# cpu.net
KiCad netlist of a schematic drawn in Altium Designer
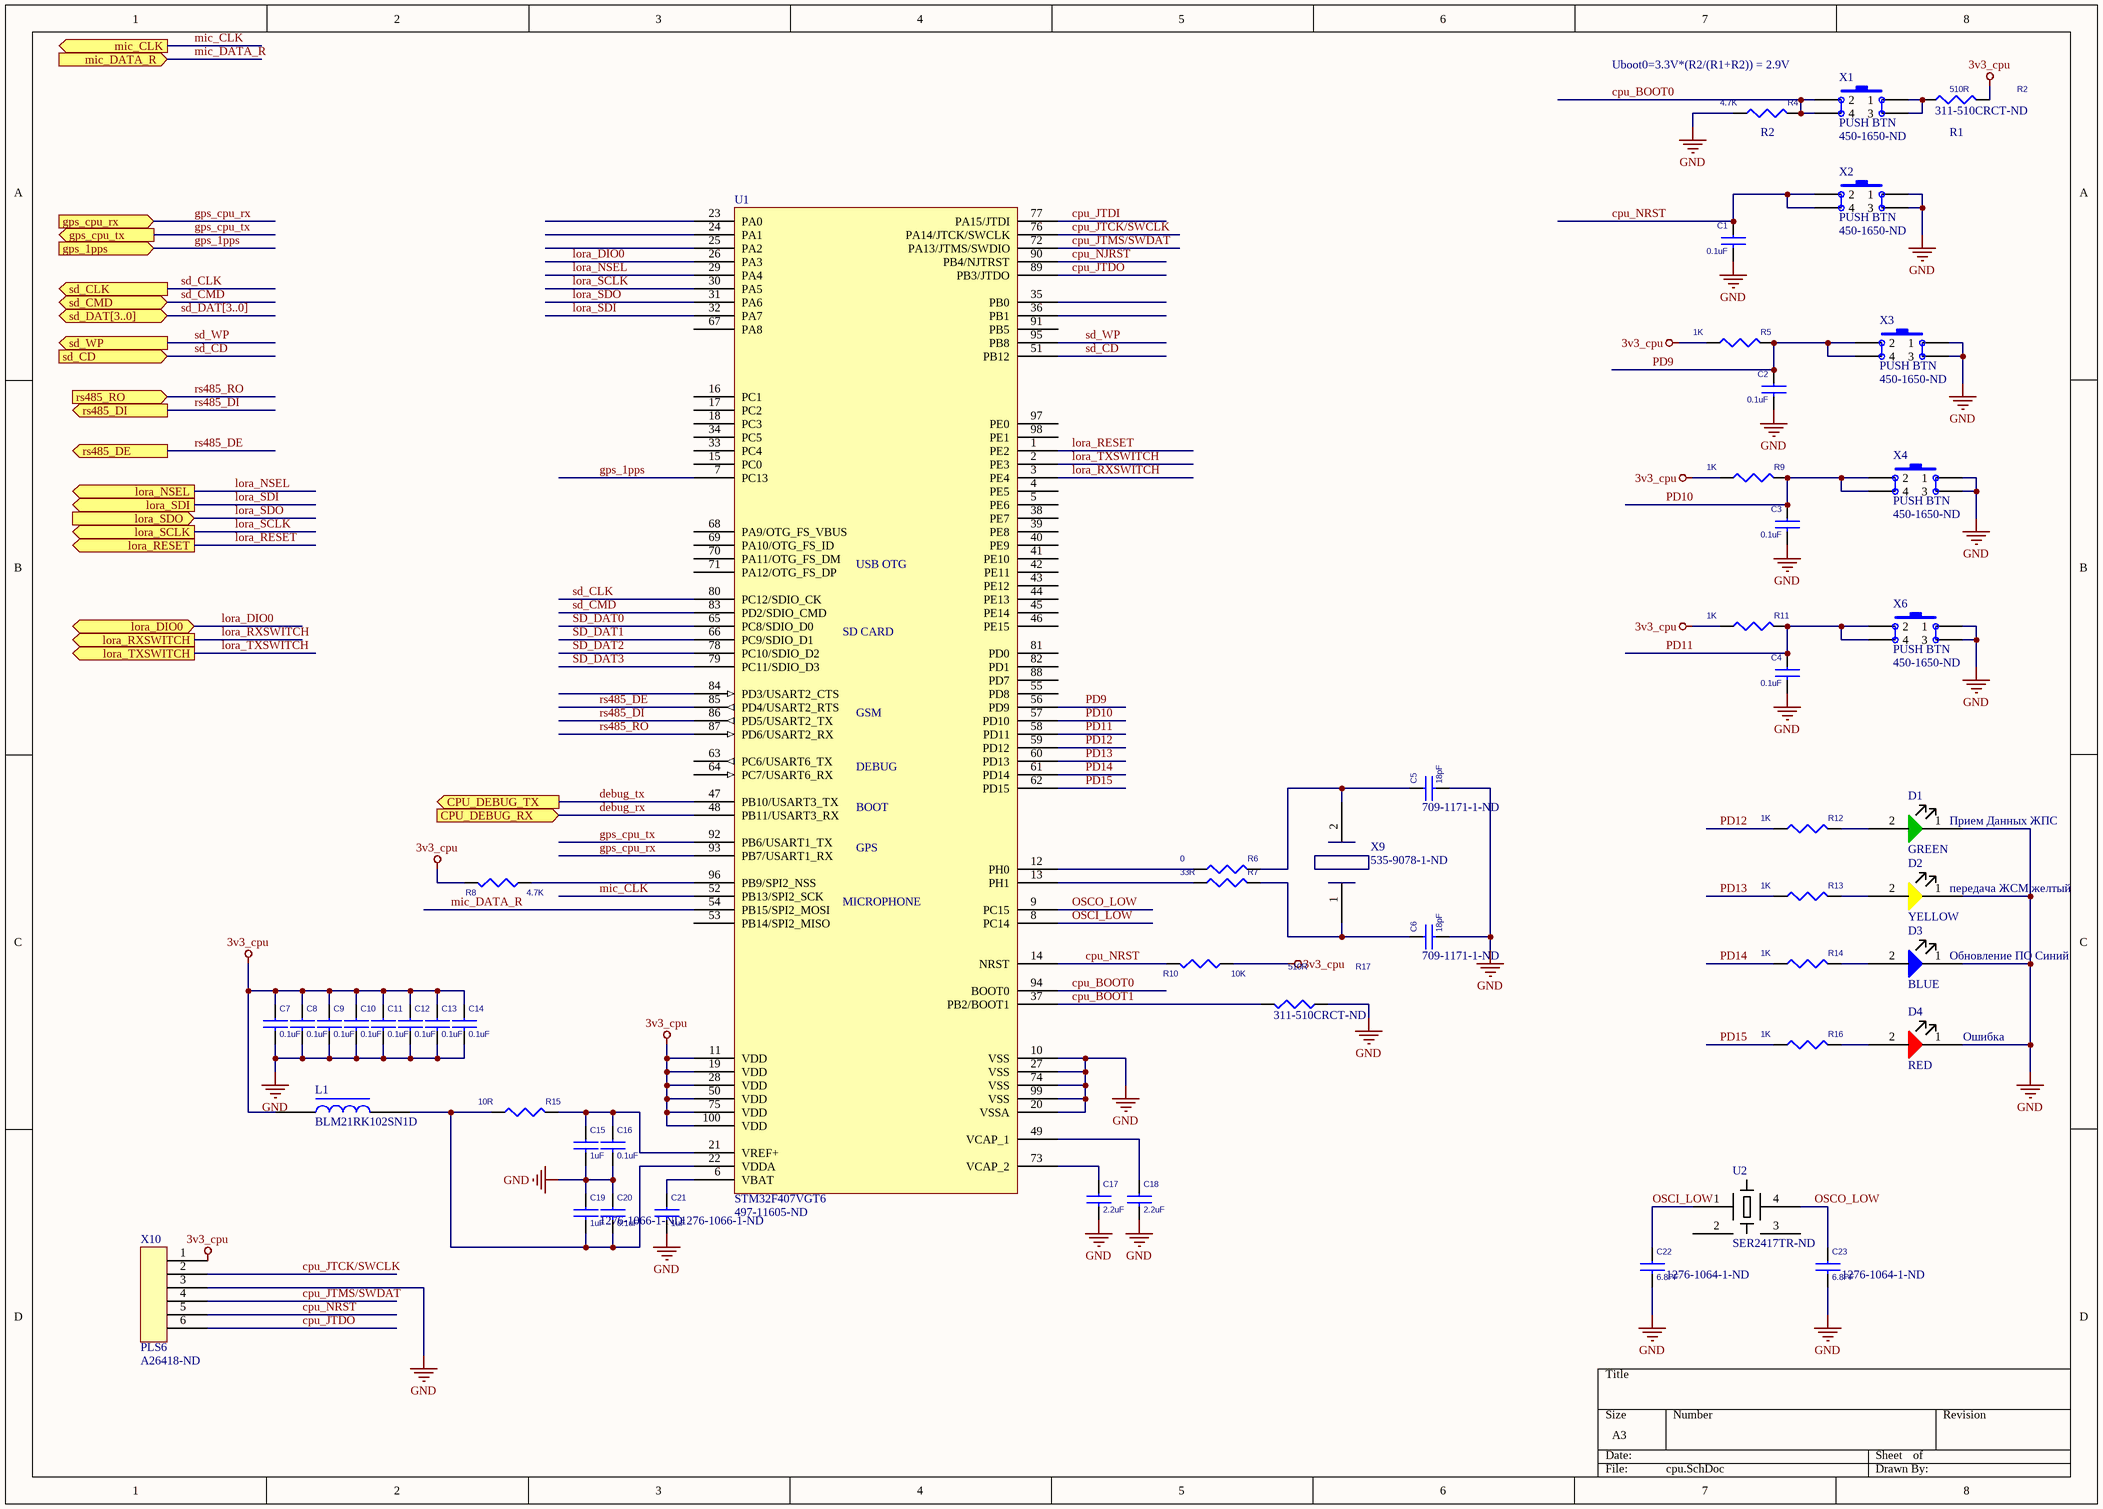
[diagram p0: cpu.SchDoc]

(export (version "E")
  (design (tool "Eeschema 10.0.6"))
  (components
    (comp (ref "C1")
      (value "0.1uF")
      (footprint "CAPC2012X09M")
      (description "CAP CER 0.1UF 25V 10% X7R 0805")
      (libsource (lib "Capacitors") (part "CAP_SMD_0.1UF_10%"))
    )
    (comp (ref "C2")
      (value "0.1uF")
      (footprint "CAPC2012X09M")
      (description "CAP CER 0.1UF 25V 10% X7R 0805")
      (libsource (lib "Capacitors") (part "CAP_SMD_0.1UF_10%"))
    )
    (comp (ref "C3")
      (value "0.1uF")
      (footprint "CAPC2012X09M")
      (description "CAP CER 0.1UF 25V 10% X7R 0805")
      (libsource (lib "Capacitors") (part "CAP_SMD_0.1UF_10%"))
    )
    (comp (ref "C4")
      (value "0.1uF")
      (footprint "CAPC2012X09M")
      (description "CAP CER 0.1UF 25V 10% X7R 0805")
      (libsource (lib "Capacitors") (part "CAP_SMD_0.1UF_10%"))
    )
    (comp (ref "C5")
      (value "18pF")
      (footprint "CAPC2012X09M")
      (description "CAP CER 27PF 200V 5% NP0 0805")
      (fields (field (name "SUPPLIER PART NUMBER 1") "709-1171-1-ND"))
      (libsource (lib "Capacitors") (part "CAP_SMD_18PF_5%"))
    )
    (comp (ref "C6")
      (value "18pF")
      (footprint "CAPC2012X09M")
      (description "CAP CER 27PF 200V 5% NP0 0805")
      (fields (field (name "SUPPLIER PART NUMBER 1") "709-1171-1-ND"))
      (libsource (lib "Capacitors") (part "CAP_SMD_18PF_5%"))
    )
    (comp (ref "C7")
      (value "0.1uF")
      (footprint "CAPC2012X09M")
      (description "CAP CER 0.1UF 25V 10% X7R 0805")
      (libsource (lib "Capacitors") (part "CAP_SMD_0.1UF_10%"))
    )
    (comp (ref "C8")
      (value "0.1uF")
      (footprint "CAPC2012X09M")
      (description "CAP CER 0.1UF 25V 10% X7R 0805")
      (libsource (lib "Capacitors") (part "CAP_SMD_0.1UF_10%"))
    )
    (comp (ref "C9")
      (value "0.1uF")
      (footprint "CAPC2012X09M")
      (description "CAP CER 0.1UF 25V 10% X7R 0805")
      (libsource (lib "Capacitors") (part "CAP_SMD_0.1UF_10%"))
    )
    (comp (ref "C10")
      (value "0.1uF")
      (footprint "CAPC2012X09M")
      (description "CAP CER 0.1UF 25V 10% X7R 0805")
      (libsource (lib "Capacitors") (part "CAP_SMD_0.1UF_10%"))
    )
    (comp (ref "C11")
      (value "0.1uF")
      (footprint "CAPC2012X09M")
      (description "CAP CER 0.1UF 25V 10% X7R 0805")
      (libsource (lib "Capacitors") (part "CAP_SMD_0.1UF_10%"))
    )
    (comp (ref "C12")
      (value "0.1uF")
      (footprint "CAPC2012X09M")
      (description "CAP CER 0.1UF 25V 10% X7R 0805")
      (libsource (lib "Capacitors") (part "CAP_SMD_0.1UF_10%"))
    )
    (comp (ref "C13")
      (value "0.1uF")
      (footprint "CAPC2012X09M")
      (description "CAP CER 0.1UF 25V 10% X7R 0805")
      (libsource (lib "Capacitors") (part "CAP_SMD_0.1UF_10%"))
    )
    (comp (ref "C14")
      (value "0.1uF")
      (footprint "CAPC2012X09M")
      (description "CAP CER 0.1UF 25V 10% X7R 0805")
      (libsource (lib "Capacitors") (part "CAP_SMD_0.1UF_10%"))
    )
    (comp (ref "C15")
      (value "1uF")
      (footprint "CAPC2012X09M")
      (description "MLCC; 1uF; 25V; X7R; ±10%; SMD; 0805;")
      (libsource (lib "Capacitors") (part "CAP_SMD_1uF_10%"))
    )
    (comp (ref "C16")
      (value "0.1uF")
      (footprint "CAPC2012X09M")
      (description "CAP CER 0.1UF 25V 10% X7R 0805")
      (libsource (lib "Capacitors") (part "CAP_SMD_0.1UF_10%"))
    )
    (comp (ref "C17")
      (value "2.2uF")
      (footprint "CAPC2012X09M")
      (description "CAP CER 2.2UF 16V 10% X5R 0805")
      (libsource (lib "Capacitors") (part "CAP_SMD_2.2uF_10%"))
    )
    (comp (ref "C18")
      (value "2.2uF")
      (footprint "CAPC2012X09M")
      (description "CAP CER 2.2UF 16V 10% X5R 0805")
      (libsource (lib "Capacitors") (part "CAP_SMD_2.2uF_10%"))
    )
    (comp (ref "C19")
      (value "1uF")
      (footprint "CAPC2012X09M")
      (description "MLCC; 1uF; 25V; X7R; ±10%; SMD; 0805;")
      (fields (field (name "SUPPLIER PART NUMBER 1") "1276-1066-1-ND"))
      (libsource (lib "Capacitors") (part "CAP_SMD_1uF_10%"))
    )
    (comp (ref "C20")
      (value "0.1uF")
      (footprint "CAPC2012X09M")
      (description "CAP CER 0.1UF 25V 10% X7R 0805")
      (libsource (lib "Capacitors") (part "CAP_SMD_0.1UF_10%"))
    )
    (comp (ref "C21")
      (value "1uF")
      (footprint "CAPC2012X09M")
      (description "MLCC; 1uF; 25V; X7R; ±10%; SMD; 0805;")
      (fields (field (name "SUPPLIER PART NUMBER 1") "1276-1066-1-ND"))
      (libsource (lib "Capacitors") (part "CAP_SMD_1uF_10%"))
    )
    (comp (ref "C22")
      (value "6.8PF")
      (footprint "CAPC2012X09M")
      (description "CAP MLCC 6.8PF 50V 5% NP0 0805")
      (fields (field (name "SUPPLIER PART NUMBER 1") "1276-1064-1-ND"))
      (libsource (lib "Capacitors") (part "CAP_SMD_6.8PF_5%"))
    )
    (comp (ref "C23")
      (value "6.8PF")
      (footprint "CAPC2012X09M")
      (description "CAP MLCC 6.8PF 50V 5% NP0 0805")
      (fields (field (name "SUPPLIER PART NUMBER 1") "1276-1064-1-ND"))
      (libsource (lib "Capacitors") (part "CAP_SMD_6.8PF_5%"))
    )
    (comp (ref "D1")
      (value "GREEN")
      (footprint "DIOC2012X11N")
      (libsource (lib "Passive") (part "LED_GREEN"))
    )
    (comp (ref "D2")
      (value "YELLOW")
      (footprint "DIOC2012X11N")
      (libsource (lib "Passive") (part "LED_YELLOW"))
    )
    (comp (ref "D3") (value "BLUE") (footprint "DIOC2012X11N") (libsource (lib "Passive") (part "LED_BLUE")))
    (comp (ref "D4") (value "RED") (footprint "DIOC2012X11N") (libsource (lib "Passive") (part "LED_RED")))
    (comp (ref "L1")
      (value "BLM21RK102SN1D")
      (footprint "DIOC2012X11N")
      (libsource (lib "Passive") (part "BLM21RK102SN1D"))
    )
    (comp (ref "R2")
      (value "510R")
      (footprint "RESC2013X06M")
      (description "RES - 510 OHM, 5%, 1/8W, 0805 SMD")
      (fields (field (name "SUPPLIER PART NUMBER 1") "311-510CRCT-ND"))
      (libsource (lib "Resistors") (part "RES_SMD_510_5%"))
    )
    (comp (ref "R4")
      (value "4.7K")
      (footprint "RESC2013X06M")
      (description "RES 4.7K OHM 1/8W 1% 0805 SMD")
      (libsource (lib "Resistors") (part "RES_SMD_4.7K_1%"))
    )
    (comp (ref "R5")
      (value "1K")
      (footprint "RESC2013X06M")
      (description "RES - 1K OHM, 5%, 1/8W, 0805 SMD")
      (libsource (lib "Resistors") (part "RES_SMD_1K_5%"))
    )
    (comp (ref "R6")
      (value "0")
      (footprint "RESC2013X06M")
      (description "RES 0.0 OHM 1/8W JUMP 0805 SMD")
      (libsource (lib "Resistors") (part "RES_SMD_0"))
    )
    (comp (ref "R7")
      (value "33R")
      (footprint "RESC2013X06M")
      (description "RES - 33 OHM, 5%, 1/8W, 0805 SMD")
      (libsource (lib "Resistors") (part "RES_SMD_33R_5%"))
    )
    (comp (ref "R8")
      (value "4.7K")
      (footprint "RESC2013X06M")
      (description "RES 4.7K OHM 1/8W 1% 0805 SMD")
      (libsource (lib "Resistors") (part "RES_SMD_4.7K_1%"))
    )
    (comp (ref "R9")
      (value "1K")
      (footprint "RESC2013X06M")
      (description "RES - 1K OHM, 5%, 1/8W, 0805 SMD")
      (libsource (lib "Resistors") (part "RES_SMD_1K_5%"))
    )
    (comp (ref "R10")
      (value "10K")
      (footprint "RESC2013X06M")
      (description "RES 10K OHM 1/8W 5% 0805 SMD")
      (libsource (lib "Resistors") (part "RES_SMD_10K_5%"))
    )
    (comp (ref "R11")
      (value "1K")
      (footprint "RESC2013X06M")
      (description "RES - 1K OHM, 5%, 1/8W, 0805 SMD")
      (libsource (lib "Resistors") (part "RES_SMD_1K_5%"))
    )
    (comp (ref "R12")
      (value "1K")
      (footprint "RESC2013X06M")
      (description "RES - 1K OHM, 5%, 1/8W, 0805 SMD")
      (libsource (lib "Resistors") (part "RES_SMD_1K_5%"))
    )
    (comp (ref "R13")
      (value "1K")
      (footprint "RESC2013X06M")
      (description "RES - 1K OHM, 5%, 1/8W, 0805 SMD")
      (libsource (lib "Resistors") (part "RES_SMD_1K_5%"))
    )
    (comp (ref "R14")
      (value "1K")
      (footprint "RESC2013X06M")
      (description "RES - 1K OHM, 5%, 1/8W, 0805 SMD")
      (libsource (lib "Resistors") (part "RES_SMD_1K_5%"))
    )
    (comp (ref "R15")
      (value "10R")
      (footprint "RESC2013X06M")
      (description "RES 10 OHM 1/8W 1% 0805 SMD")
      (libsource (lib "Resistors") (part "RES_SMD_10R_5%"))
    )
    (comp (ref "R16")
      (value "1K")
      (footprint "RESC2013X06M")
      (description "RES - 1K OHM, 5%, 1/8W, 0805 SMD")
      (libsource (lib "Resistors") (part "RES_SMD_1K_5%"))
    )
    (comp (ref "R17")
      (value "510R")
      (footprint "RESC2013X06M")
      (description "RES - 510 OHM, 5%, 1/8W, 0805 SMD")
      (fields (field (name "SUPPLIER PART NUMBER 1") "311-510CRCT-ND"))
      (libsource (lib "Resistors") (part "RES_SMD_510_5%"))
    )
    (comp (ref "U1")
      (value "STM32F407VGT6")
      (footprint "TSQFP50P1600X1600X160-100M")
      (fields (field (name "SUPPLIER PART NUMBER 1") "497-11605-ND"))
      (libsource (lib "TruthEar") (part "STM32F407VGT6"))
    )
    (comp (ref "U2")
      (value "32.768KHZ")
      (footprint "SOJ550P380X254-4M")
      (fields (field (name "SUPPLIER PART NUMBER 1") "SER2417TR-ND"))
      (libsource (lib "TruthEar") (part "MC-306"))
    )
    (comp (ref "X1")
      (value "PUSH BTN")
      (footprint "PUSHBTN")
      (fields (field (name "SUPPLIER PART NUMBER 1") "450-1650-ND"))
      (libsource (lib "TruthEar") (part "SW1"))
    )
    (comp (ref "X2")
      (value "PUSH BTN")
      (footprint "PUSHBTN")
      (fields (field (name "SUPPLIER PART NUMBER 1") "450-1650-ND"))
      (libsource (lib "TruthEar") (part "SW1"))
    )
    (comp (ref "X3")
      (value "PUSH BTN")
      (footprint "PUSHBTN")
      (fields (field (name "SUPPLIER PART NUMBER 1") "450-1650-ND"))
      (libsource (lib "TruthEar") (part "SW1"))
    )
    (comp (ref "X4")
      (value "PUSH BTN")
      (footprint "PUSHBTN")
      (fields (field (name "SUPPLIER PART NUMBER 1") "450-1650-ND"))
      (libsource (lib "TruthEar") (part "SW1"))
    )
    (comp (ref "X6")
      (value "PUSH BTN")
      (footprint "PUSHBTN")
      (fields (field (name "SUPPLIER PART NUMBER 1") "450-1650-ND"))
      (libsource (lib "TruthEar") (part "SW1"))
    )
    (comp (ref "X9")
      (value "25.000Mhz")
      (footprint "SODFL1270X420-2L")
      (fields (field (name "SUPPLIER PART NUMBER 1") "535-9078-1-ND"))
      (libsource (lib "TruthEar") (part "OSC25M"))
    )
    (comp (ref "X10")
      (value "PLS6")
      (footprint "PLS6")
      (fields (field (name "SUPPLIER PART NUMBER 1") "A26418-ND"))
      (libsource (lib "Connectors") (part "PLS6"))
    )
  )
  (nets
    (net (code "5") (name "/OSCI_LOW") (class "Default")
      (node (ref "C22") (pin "1") (pinfunction "1_1") (pintype "passive"))
      (node (ref "U1") (pin "8") (pinfunction "PC14_8") (pintype "passive"))
      (node (ref "U2") (pin "1") (pinfunction "OSC1_1") (pintype "power_in"))
    )
    (net (code "6") (name "/OSCO_LOW") (class "Default")
      (node (ref "C23") (pin "1") (pinfunction "1_1") (pintype "passive"))
      (node (ref "U1") (pin "9") (pinfunction "PC15_9") (pintype "passive"))
      (node (ref "U2") (pin "4") (pinfunction "OSC2_4") (pintype "power_in"))
    )
    (net (code "7") (name "/PD9") (class "Default")
      (node (ref "C2") (pin "1") (pinfunction "1_1") (pintype "passive"))
      (node (ref "R5") (pin "2") (pinfunction "2_2") (pintype "passive"))
      (node (ref "U1") (pin "56") (pinfunction "PD9_56") (pintype "passive"))
      (node (ref "X3") (pin "2") (pinfunction "2_2") (pintype "passive"))
      (node (ref "X3") (pin "4") (pinfunction "4_4") (pintype "passive"))
    )
    (net (code "8") (name "/PD10") (class "Default")
      (node (ref "C3") (pin "1") (pinfunction "1_1") (pintype "passive"))
      (node (ref "R9") (pin "2") (pinfunction "2_2") (pintype "passive"))
      (node (ref "U1") (pin "57") (pinfunction "PD10_57") (pintype "passive"))
      (node (ref "X4") (pin "2") (pinfunction "2_2") (pintype "passive"))
      (node (ref "X4") (pin "4") (pinfunction "4_4") (pintype "passive"))
    )
    (net (code "9") (name "/PD11") (class "Default")
      (node (ref "C4") (pin "1") (pinfunction "1_1") (pintype "passive"))
      (node (ref "R11") (pin "2") (pinfunction "2_2") (pintype "passive"))
      (node (ref "U1") (pin "58") (pinfunction "PD11_58") (pintype "passive"))
      (node (ref "X6") (pin "2") (pinfunction "2_2") (pintype "passive"))
      (node (ref "X6") (pin "4") (pinfunction "4_4") (pintype "passive"))
    )
    (net (code "10") (name "/PD12") (class "Default")
      (node (ref "R12") (pin "1") (pinfunction "1_1") (pintype "passive"))
      (node (ref "U1") (pin "59") (pinfunction "PD12_59") (pintype "passive"))
    )
    (net (code "11") (name "/PD13") (class "Default")
      (node (ref "R13") (pin "1") (pinfunction "1_1") (pintype "passive"))
      (node (ref "U1") (pin "60") (pinfunction "PD13_60") (pintype "passive"))
    )
    (net (code "12") (name "/PD14") (class "Default")
      (node (ref "R14") (pin "1") (pinfunction "1_1") (pintype "passive"))
      (node (ref "U1") (pin "61") (pinfunction "PD14_61") (pintype "passive"))
    )
    (net (code "13") (name "/PD15") (class "Default")
      (node (ref "R16") (pin "1") (pinfunction "1_1") (pintype "passive"))
      (node (ref "U1") (pin "62") (pinfunction "PD15_62") (pintype "passive"))
    )
    (net (code "14") (name "/SD_DAT0") (class "Default")
      (node (ref "U1") (pin "65") (pinfunction "PC8/SDIO_D0_65") (pintype "passive"))
    )
    (net (code "15") (name "/SD_DAT1") (class "Default")
      (node (ref "U1") (pin "66") (pinfunction "PC9/SDIO_D1_66") (pintype "passive"))
    )
    (net (code "16") (name "/SD_DAT2") (class "Default")
      (node (ref "U1") (pin "78") (pinfunction "PC10/SDIO_D2_78") (pintype "passive"))
    )
    (net (code "17") (name "/SD_DAT3") (class "Default")
      (node (ref "U1") (pin "79") (pinfunction "PC11/SDIO_D3_79") (pintype "passive"))
    )
    (net (code "18") (name "/cpu_BOOT0") (class "Default")
      (node (ref "R4") (pin "2") (pinfunction "2_2") (pintype "passive"))
      (node (ref "U1") (pin "94") (pinfunction "BOOT0_94") (pintype "passive"))
      (node (ref "X1") (pin "2") (pinfunction "2_2") (pintype "passive"))
      (node (ref "X1") (pin "4") (pinfunction "4_4") (pintype "passive"))
    )
    (net (code "19") (name "/cpu_BOOT1") (class "Default")
      (node (ref "R17") (pin "2") (pinfunction "2_2") (pintype "passive"))
      (node (ref "U1") (pin "37") (pinfunction "PB2/BOOT1_37") (pintype "passive"))
    )
    (net (code "20") (name "/cpu_JTCK{slash}SWCLK") (class "Default")
      (node (ref "U1") (pin "76") (pinfunction "PA14/JTCK/SWCLK_76") (pintype "passive"))
      (node (ref "X10") (pin "2") (pinfunction "2_2") (pintype "power_in"))
    )
    (net (code "21") (name "/cpu_JTDI") (class "Default")
      (node (ref "U1") (pin "77") (pinfunction "PA15/JTDI_77") (pintype "passive"))
    )
    (net (code "22") (name "/cpu_JTDO") (class "Default")
      (node (ref "U1") (pin "89") (pinfunction "PB3/JTDO_89") (pintype "passive"))
      (node (ref "X10") (pin "6") (pinfunction "6_6") (pintype "power_in"))
    )
    (net (code "23") (name "/cpu_JTMS{slash}SWDAT") (class "Default")
      (node (ref "U1") (pin "72") (pinfunction "PA13/JTMS/SWDIO_72") (pintype "passive"))
      (node (ref "X10") (pin "4") (pinfunction "4_4") (pintype "power_in"))
    )
    (net (code "24") (name "/cpu_NJRST") (class "Default")
      (node (ref "U1") (pin "90") (pinfunction "PB4/NJTRST_90") (pintype "passive"))
    )
    (net (code "25") (name "/cpu_NRST") (class "Default")
      (node (ref "C1") (pin "1") (pinfunction "1_1") (pintype "passive"))
      (node (ref "R10") (pin "2") (pinfunction "2_2") (pintype "passive"))
      (node (ref "U1") (pin "14") (pinfunction "NRST_14") (pintype "passive"))
      (node (ref "X10") (pin "5") (pinfunction "5_5") (pintype "power_in"))
      (node (ref "X2") (pin "2") (pinfunction "2_2") (pintype "passive"))
      (node (ref "X2") (pin "4") (pinfunction "4_4") (pintype "passive"))
    )
    (net (code "26") (name "/debug_rx") (class "Default")
      (node (ref "U1") (pin "48") (pinfunction "PB11/USART3_RX_48") (pintype "passive"))
    )
    (net (code "27") (name "/debug_tx") (class "Default")
      (node (ref "U1") (pin "47") (pinfunction "PB10/USART3_TX_47") (pintype "passive"))
    )
    (net (code "28") (name "/gps_1pps") (class "Default")
      (node (ref "U1") (pin "7") (pinfunction "PC13_7") (pintype "passive"))
    )
    (net (code "29") (name "/gps_cpu_rx") (class "Default")
      (node (ref "U1") (pin "93") (pinfunction "PB7/USART1_RX_93") (pintype "passive"))
    )
    (net (code "30") (name "/gps_cpu_tx") (class "Default")
      (node (ref "U1") (pin "92") (pinfunction "PB6/USART1_TX_92") (pintype "passive"))
    )
    (net (code "31") (name "/lora_DIO0") (class "Default")
      (node (ref "U1") (pin "26") (pinfunction "PA3_26") (pintype "passive"))
    )
    (net (code "32") (name "/lora_NSEL") (class "Default")
      (node (ref "U1") (pin "29") (pinfunction "PA4_29") (pintype "passive"))
    )
    (net (code "33") (name "/lora_RESET") (class "Default")
      (node (ref "U1") (pin "1") (pinfunction "PE2_1") (pintype "passive"))
    )
    (net (code "34") (name "/lora_RXSWITCH") (class "Default")
      (node (ref "U1") (pin "3") (pinfunction "PE4_3") (pintype "passive"))
    )
    (net (code "35") (name "/lora_SCLK") (class "Default")
      (node (ref "U1") (pin "30") (pinfunction "PA5_30") (pintype "passive"))
    )
    (net (code "36") (name "/lora_SDI") (class "Default")
      (node (ref "U1") (pin "32") (pinfunction "PA7_32") (pintype "passive"))
    )
    (net (code "37") (name "/lora_SDO") (class "Default")
      (node (ref "U1") (pin "31") (pinfunction "PA6_31") (pintype "passive"))
    )
    (net (code "38") (name "/lora_TXSWITCH") (class "Default")
      (node (ref "U1") (pin "2") (pinfunction "PE3_2") (pintype "passive"))
    )
    (net (code "39") (name "/mic_CLK") (class "Default")
      (node (ref "U1") (pin "52") (pinfunction "PB13/SPI2_SCK_52") (pintype "passive"))
    )
    (net (code "40") (name "/mic_DATA_R") (class "Default")
      (node (ref "U1") (pin "54") (pinfunction "PB15/SPI2_MOSI_54") (pintype "passive"))
    )
    (net (code "41") (name "/rs485_DE") (class "Default")
      (node (ref "U1") (pin "85") (pinfunction "PD4/USART2_RTS_85") (pintype "output"))
    )
    (net (code "42") (name "/rs485_DI") (class "Default")
      (node (ref "U1") (pin "86") (pinfunction "PD5/USART2_TX_86") (pintype "output"))
    )
    (net (code "43") (name "/rs485_RO") (class "Default")
      (node (ref "U1") (pin "87") (pinfunction "PD6/USART2_RX_87") (pintype "input"))
    )
    (net (code "44") (name "/sd_CD") (class "Default")
      (node (ref "U1") (pin "51") (pinfunction "PB12_51") (pintype "passive"))
    )
    (net (code "45") (name "/sd_CLK") (class "Default")
      (node (ref "U1") (pin "80") (pinfunction "PC12/SDIO_CK_80") (pintype "passive"))
    )
    (net (code "46") (name "/sd_CMD") (class "Default")
      (node (ref "U1") (pin "83") (pinfunction "PD2/SDIO_CMD_83") (pintype "passive"))
    )
    (net (code "48") (name "/sd_WP") (class "Default")
      (node (ref "U1") (pin "95") (pinfunction "PB8_95") (pintype "passive"))
    )
    (net (code "49") (name "3v3_cpu") (class "Default")
      (node (ref "C10") (pin "1") (pinfunction "1_1") (pintype "passive"))
      (node (ref "C11") (pin "1") (pinfunction "1_1") (pintype "passive"))
      (node (ref "C12") (pin "1") (pinfunction "1_1") (pintype "passive"))
      (node (ref "C13") (pin "1") (pinfunction "1_1") (pintype "passive"))
      (node (ref "C14") (pin "1") (pinfunction "1_1") (pintype "passive"))
      (node (ref "C7") (pin "1") (pinfunction "1_1") (pintype "passive"))
      (node (ref "C8") (pin "1") (pinfunction "1_1") (pintype "passive"))
      (node (ref "C9") (pin "1") (pinfunction "1_1") (pintype "passive"))
      (node (ref "L1") (pin "1") (pinfunction "1_1") (pintype "passive"))
      (node (ref "R10") (pin "1") (pinfunction "1_1") (pintype "passive"))
      (node (ref "R11") (pin "1") (pinfunction "1_1") (pintype "passive"))
      (node (ref "R2") (pin "1") (pinfunction "1_1") (pintype "passive"))
      (node (ref "R5") (pin "1") (pinfunction "1_1") (pintype "passive"))
      (node (ref "R8") (pin "2") (pinfunction "2_2") (pintype "passive"))
      (node (ref "R9") (pin "1") (pinfunction "1_1") (pintype "passive"))
      (node (ref "U1") (pin "100") (pinfunction "VDD_100") (pintype "passive"))
      (node (ref "U1") (pin "11") (pinfunction "VDD_11") (pintype "passive"))
      (node (ref "U1") (pin "19") (pinfunction "VDD_19") (pintype "passive"))
      (node (ref "U1") (pin "28") (pinfunction "VDD_28") (pintype "passive"))
      (node (ref "U1") (pin "50") (pinfunction "VDD_50") (pintype "passive"))
      (node (ref "U1") (pin "75") (pinfunction "VDD_75") (pintype "passive"))
      (node (ref "X10") (pin "1") (pinfunction "1_1") (pintype "power_in"))
    )
    (net (code "50") (name "GND") (class "Default")
      (node (ref "C1") (pin "2") (pinfunction "2_2") (pintype "passive"))
      (node (ref "C10") (pin "2") (pinfunction "2_2") (pintype "passive"))
      (node (ref "C11") (pin "2") (pinfunction "2_2") (pintype "passive"))
      (node (ref "C12") (pin "2") (pinfunction "2_2") (pintype "passive"))
      (node (ref "C13") (pin "2") (pinfunction "2_2") (pintype "passive"))
      (node (ref "C14") (pin "2") (pinfunction "2_2") (pintype "passive"))
      (node (ref "C15") (pin "2") (pinfunction "2_2") (pintype "passive"))
      (node (ref "C16") (pin "2") (pinfunction "2_2") (pintype "passive"))
      (node (ref "C17") (pin "2") (pinfunction "2_2") (pintype "passive"))
      (node (ref "C18") (pin "2") (pinfunction "2_2") (pintype "passive"))
      (node (ref "C19") (pin "1") (pinfunction "1_1") (pintype "passive"))
      (node (ref "C2") (pin "2") (pinfunction "2_2") (pintype "passive"))
      (node (ref "C20") (pin "1") (pinfunction "1_1") (pintype "passive"))
      (node (ref "C21") (pin "2") (pinfunction "2_2") (pintype "passive"))
      (node (ref "C22") (pin "2") (pinfunction "2_2") (pintype "passive"))
      (node (ref "C23") (pin "2") (pinfunction "2_2") (pintype "passive"))
      (node (ref "C3") (pin "2") (pinfunction "2_2") (pintype "passive"))
      (node (ref "C4") (pin "2") (pinfunction "2_2") (pintype "passive"))
      (node (ref "C5") (pin "2") (pinfunction "2_2") (pintype "passive"))
      (node (ref "C6") (pin "2") (pinfunction "2_2") (pintype "passive"))
      (node (ref "C7") (pin "2") (pinfunction "2_2") (pintype "passive"))
      (node (ref "C8") (pin "2") (pinfunction "2_2") (pintype "passive"))
      (node (ref "C9") (pin "2") (pinfunction "2_2") (pintype "passive"))
      (node (ref "D1") (pin "1") (pinfunction "C_1") (pintype "passive"))
      (node (ref "D2") (pin "1") (pinfunction "C_1") (pintype "passive"))
      (node (ref "D3") (pin "1") (pinfunction "C_1") (pintype "passive"))
      (node (ref "D4") (pin "1") (pinfunction "C_1") (pintype "passive"))
      (node (ref "R17") (pin "1") (pinfunction "1_1") (pintype "passive"))
      (node (ref "R4") (pin "1") (pinfunction "1_1") (pintype "passive"))
      (node (ref "U1") (pin "10") (pinfunction "VSS_10") (pintype "passive"))
      (node (ref "U1") (pin "20") (pinfunction "VSSA_20") (pintype "passive"))
      (node (ref "U1") (pin "27") (pinfunction "VSS_27") (pintype "passive"))
      (node (ref "U1") (pin "74") (pinfunction "VSS_74") (pintype "passive"))
      (node (ref "U1") (pin "99") (pinfunction "VSS_99") (pintype "passive"))
      (node (ref "X10") (pin "3") (pinfunction "3_3") (pintype "power_in"))
      (node (ref "X2") (pin "1") (pinfunction "1_1") (pintype "passive"))
      (node (ref "X2") (pin "3") (pinfunction "3_3") (pintype "passive"))
      (node (ref "X3") (pin "1") (pinfunction "1_1") (pintype "passive"))
      (node (ref "X3") (pin "3") (pinfunction "3_3") (pintype "passive"))
      (node (ref "X4") (pin "1") (pinfunction "1_1") (pintype "passive"))
      (node (ref "X4") (pin "3") (pinfunction "3_3") (pintype "passive"))
      (node (ref "X6") (pin "1") (pinfunction "1_1") (pintype "passive"))
      (node (ref "X6") (pin "3") (pinfunction "3_3") (pintype "passive"))
    )
    (net (code "51") (name "Net-(C5-Pad1)") (class "Default")
      (node (ref "C5") (pin "1") (pinfunction "1_1") (pintype "passive"))
      (node (ref "R6") (pin "2") (pinfunction "2_2") (pintype "passive"))
      (node (ref "X9") (pin "2") (pinfunction "2_2") (pintype "power_in"))
    )
    (net (code "52") (name "Net-(C6-Pad1)") (class "Default")
      (node (ref "C6") (pin "1") (pinfunction "1_1") (pintype "passive"))
      (node (ref "R7") (pin "2") (pinfunction "2_2") (pintype "passive"))
      (node (ref "X9") (pin "1") (pinfunction "1_1") (pintype "power_in"))
    )
    (net (code "53") (name "Net-(D1-A)") (class "Default")
      (node (ref "D1") (pin "2") (pinfunction "A_2") (pintype "passive"))
      (node (ref "R12") (pin "2") (pinfunction "2_2") (pintype "passive"))
    )
    (net (code "54") (name "Net-(D2-A)") (class "Default")
      (node (ref "D2") (pin "2") (pinfunction "A_2") (pintype "passive"))
      (node (ref "R13") (pin "2") (pinfunction "2_2") (pintype "passive"))
    )
    (net (code "55") (name "Net-(D3-A)") (class "Default")
      (node (ref "D3") (pin "2") (pinfunction "A_2") (pintype "passive"))
      (node (ref "R14") (pin "2") (pinfunction "2_2") (pintype "passive"))
    )
    (net (code "56") (name "Net-(D4-A)") (class "Default")
      (node (ref "D4") (pin "2") (pinfunction "A_2") (pintype "passive"))
      (node (ref "R16") (pin "2") (pinfunction "2_2") (pintype "passive"))
    )
    (net (code "57") (name "Net-(R2-Pad2)") (class "Default")
      (node (ref "R2") (pin "2") (pinfunction "2_2") (pintype "passive"))
      (node (ref "X1") (pin "1") (pinfunction "1_1") (pintype "passive"))
      (node (ref "X1") (pin "3") (pinfunction "3_3") (pintype "passive"))
    )
    (net (code "58") (name "Net-(U1-PB9{slash}SPI2_NSS)") (class "Default")
      (node (ref "R8") (pin "1") (pinfunction "1_1") (pintype "passive"))
      (node (ref "U1") (pin "96") (pinfunction "PB9/SPI2_NSS_96") (pintype "passive"))
    )
    (net (code "59") (name "Net-(U1-PH0)") (class "Default")
      (node (ref "R6") (pin "1") (pinfunction "1_1") (pintype "passive"))
      (node (ref "U1") (pin "12") (pinfunction "PH0_12") (pintype "passive"))
    )
    (net (code "60") (name "Net-(U1-PH1)") (class "Default")
      (node (ref "R7") (pin "1") (pinfunction "1_1") (pintype "passive"))
      (node (ref "U1") (pin "13") (pinfunction "PH1_13") (pintype "passive"))
    )
    (net (code "61") (name "Net-(U1-VBAT)") (class "Default")
      (node (ref "C21") (pin "1") (pinfunction "1_1") (pintype "passive"))
      (node (ref "U1") (pin "6") (pinfunction "VBAT_6") (pintype "passive"))
    )
    (net (code "62") (name "Net-(U1-VCAP_1)") (class "Default")
      (node (ref "C18") (pin "1") (pinfunction "1_1") (pintype "passive"))
      (node (ref "U1") (pin "49") (pinfunction "VCAP_1_49") (pintype "passive"))
    )
    (net (code "63") (name "Net-(U1-VCAP_2)") (class "Default")
      (node (ref "C17") (pin "1") (pinfunction "1_1") (pintype "passive"))
      (node (ref "U1") (pin "73") (pinfunction "VCAP_2_73") (pintype "passive"))
    )
    (net (code "64") (name "Net-(U1-VDDA)") (class "Default")
      (node (ref "C19") (pin "2") (pinfunction "2_2") (pintype "passive"))
      (node (ref "C20") (pin "2") (pinfunction "2_2") (pintype "passive"))
      (node (ref "L1") (pin "2") (pinfunction "2_2") (pintype "passive"))
      (node (ref "R15") (pin "1") (pinfunction "1_1") (pintype "passive"))
      (node (ref "U1") (pin "22") (pinfunction "VDDA_22") (pintype "passive"))
    )
    (net (code "65") (name "Net-(U1-VREF+)") (class "Default")
      (node (ref "C15") (pin "1") (pinfunction "1_1") (pintype "passive"))
      (node (ref "C16") (pin "1") (pinfunction "1_1") (pintype "passive"))
      (node (ref "R15") (pin "2") (pinfunction "2_2") (pintype "passive"))
      (node (ref "U1") (pin "21") (pinfunction "VREF+_21") (pintype "passive"))
    )
    (net (code "66") (name "unconnected-(U1-PA0-Pad23)") (class "Default")
      (node (ref "U1") (pin "23") (pinfunction "PA0_23") (pintype "passive"))
    )
    (net (code "67") (name "unconnected-(U1-PA1-Pad24)") (class "Default")
      (node (ref "U1") (pin "24") (pinfunction "PA1_24") (pintype "passive"))
    )
    (net (code "68") (name "unconnected-(U1-PA2-Pad25)") (class "Default")
      (node (ref "U1") (pin "25") (pinfunction "PA2_25") (pintype "passive"))
    )
    (net (code "69") (name "unconnected-(U1-PA8-Pad67)") (class "Default")
      (node (ref "U1") (pin "67") (pinfunction "PA8_67") (pintype "passive"))
    )
    (net (code "70") (name "unconnected-(U1-PA9{slash}OTG_FS_VBUS-Pad68)") (class "Default")
      (node (ref "U1") (pin "68") (pinfunction "PA9/OTG_FS_VBUS_68") (pintype "passive"))
    )
    (net (code "71") (name "unconnected-(U1-PA10{slash}OTG_FS_ID-Pad69)") (class "Default")
      (node (ref "U1") (pin "69") (pinfunction "PA10/OTG_FS_ID_69") (pintype "passive"))
    )
    (net (code "72") (name "unconnected-(U1-PA11{slash}OTG_FS_DM-Pad70)") (class "Default")
      (node (ref "U1") (pin "70") (pinfunction "PA11/OTG_FS_DM_70") (pintype "passive"))
    )
    (net (code "73") (name "unconnected-(U1-PA12{slash}OTG_FS_DP-Pad71)") (class "Default")
      (node (ref "U1") (pin "71") (pinfunction "PA12/OTG_FS_DP_71") (pintype "passive"))
    )
    (net (code "74") (name "unconnected-(U1-PB0-Pad35)") (class "Default")
      (node (ref "U1") (pin "35") (pinfunction "PB0_35") (pintype "passive"))
    )
    (net (code "75") (name "unconnected-(U1-PB1-Pad36)") (class "Default")
      (node (ref "U1") (pin "36") (pinfunction "PB1_36") (pintype "passive"))
    )
    (net (code "76") (name "unconnected-(U1-PB5-Pad91)") (class "Default")
      (node (ref "U1") (pin "91") (pinfunction "PB5_91") (pintype "passive"))
    )
    (net (code "77") (name "unconnected-(U1-PB14{slash}SPI2_MISO-Pad53)") (class "Default")
      (node (ref "U1") (pin "53") (pinfunction "PB14/SPI2_MISO_53") (pintype "passive"))
    )
    (net (code "78") (name "unconnected-(U1-PC0-Pad15)") (class "Default")
      (node (ref "U1") (pin "15") (pinfunction "PC0_15") (pintype "passive"))
    )
    (net (code "79") (name "unconnected-(U1-PC1-Pad16)") (class "Default")
      (node (ref "U1") (pin "16") (pinfunction "PC1_16") (pintype "passive"))
    )
    (net (code "80") (name "unconnected-(U1-PC2-Pad17)") (class "Default")
      (node (ref "U1") (pin "17") (pinfunction "PC2_17") (pintype "passive"))
    )
    (net (code "81") (name "unconnected-(U1-PC3-Pad18)") (class "Default")
      (node (ref "U1") (pin "18") (pinfunction "PC3_18") (pintype "passive"))
    )
    (net (code "82") (name "unconnected-(U1-PC4-Pad33)") (class "Default")
      (node (ref "U1") (pin "33") (pinfunction "PC4_33") (pintype "passive"))
    )
    (net (code "83") (name "unconnected-(U1-PC5-Pad34)") (class "Default")
      (node (ref "U1") (pin "34") (pinfunction "PC5_34") (pintype "passive"))
    )
    (net (code "84") (name "unconnected-(U1-PC6{slash}USART6_TX-Pad63)") (class "Default")
      (node (ref "U1") (pin "63") (pinfunction "PC6/USART6_TX_63") (pintype "output"))
    )
    (net (code "85") (name "unconnected-(U1-PC7{slash}USART6_RX-Pad64)") (class "Default")
      (node (ref "U1") (pin "64") (pinfunction "PC7/USART6_RX_64") (pintype "input"))
    )
    (net (code "86") (name "unconnected-(U1-PD0-Pad81)") (class "Default")
      (node (ref "U1") (pin "81") (pinfunction "PD0_81") (pintype "passive"))
    )
    (net (code "87") (name "unconnected-(U1-PD1-Pad82)") (class "Default")
      (node (ref "U1") (pin "82") (pinfunction "PD1_82") (pintype "passive"))
    )
    (net (code "88") (name "unconnected-(U1-PD3{slash}USART2_CTS-Pad84)") (class "Default")
      (node (ref "U1") (pin "84") (pinfunction "PD3/USART2_CTS_84") (pintype "input"))
    )
    (net (code "89") (name "unconnected-(U1-PD7-Pad88)") (class "Default")
      (node (ref "U1") (pin "88") (pinfunction "PD7_88") (pintype "passive"))
    )
    (net (code "90") (name "unconnected-(U1-PD8-Pad55)") (class "Default")
      (node (ref "U1") (pin "55") (pinfunction "PD8_55") (pintype "passive"))
    )
    (net (code "91") (name "unconnected-(U1-PE0-Pad97)") (class "Default")
      (node (ref "U1") (pin "97") (pinfunction "PE0_97") (pintype "passive"))
    )
    (net (code "92") (name "unconnected-(U1-PE1-Pad98)") (class "Default")
      (node (ref "U1") (pin "98") (pinfunction "PE1_98") (pintype "passive"))
    )
    (net (code "93") (name "unconnected-(U1-PE5-Pad4)") (class "Default")
      (node (ref "U1") (pin "4") (pinfunction "PE5_4") (pintype "passive"))
    )
    (net (code "94") (name "unconnected-(U1-PE6-Pad5)") (class "Default")
      (node (ref "U1") (pin "5") (pinfunction "PE6_5") (pintype "passive"))
    )
    (net (code "95") (name "unconnected-(U1-PE7-Pad38)") (class "Default")
      (node (ref "U1") (pin "38") (pinfunction "PE7_38") (pintype "passive"))
    )
    (net (code "96") (name "unconnected-(U1-PE8-Pad39)") (class "Default")
      (node (ref "U1") (pin "39") (pinfunction "PE8_39") (pintype "passive"))
    )
    (net (code "97") (name "unconnected-(U1-PE9-Pad40)") (class "Default")
      (node (ref "U1") (pin "40") (pinfunction "PE9_40") (pintype "passive"))
    )
    (net (code "98") (name "unconnected-(U1-PE10-Pad41)") (class "Default")
      (node (ref "U1") (pin "41") (pinfunction "PE10_41") (pintype "passive"))
    )
    (net (code "99") (name "unconnected-(U1-PE11-Pad42)") (class "Default")
      (node (ref "U1") (pin "42") (pinfunction "PE11_42") (pintype "passive"))
    )
    (net (code "100") (name "unconnected-(U1-PE12-Pad43)") (class "Default")
      (node (ref "U1") (pin "43") (pinfunction "PE12_43") (pintype "passive"))
    )
    (net (code "101") (name "unconnected-(U1-PE13-Pad44)") (class "Default")
      (node (ref "U1") (pin "44") (pinfunction "PE13_44") (pintype "passive"))
    )
    (net (code "102") (name "unconnected-(U1-PE14-Pad45)") (class "Default")
      (node (ref "U1") (pin "45") (pinfunction "PE14_45") (pintype "passive"))
    )
    (net (code "103") (name "unconnected-(U1-PE15-Pad46)") (class "Default")
      (node (ref "U1") (pin "46") (pinfunction "PE15_46") (pintype "passive"))
    )
    (net (code "104") (name "unconnected-(U2-NC-Pad2)") (class "Default")
      (node (ref "U2") (pin "2") (pinfunction "NC_2") (pintype "power_in"))
    )
    (net (code "105") (name "unconnected-(U2-NC-Pad3)") (class "Default")
      (node (ref "U2") (pin "3") (pinfunction "NC_3") (pintype "power_in"))
    )
  )
)
